# PlacaCalefactora_notUsed.net
KiCad netlist of a schematic drawn in EAGLE
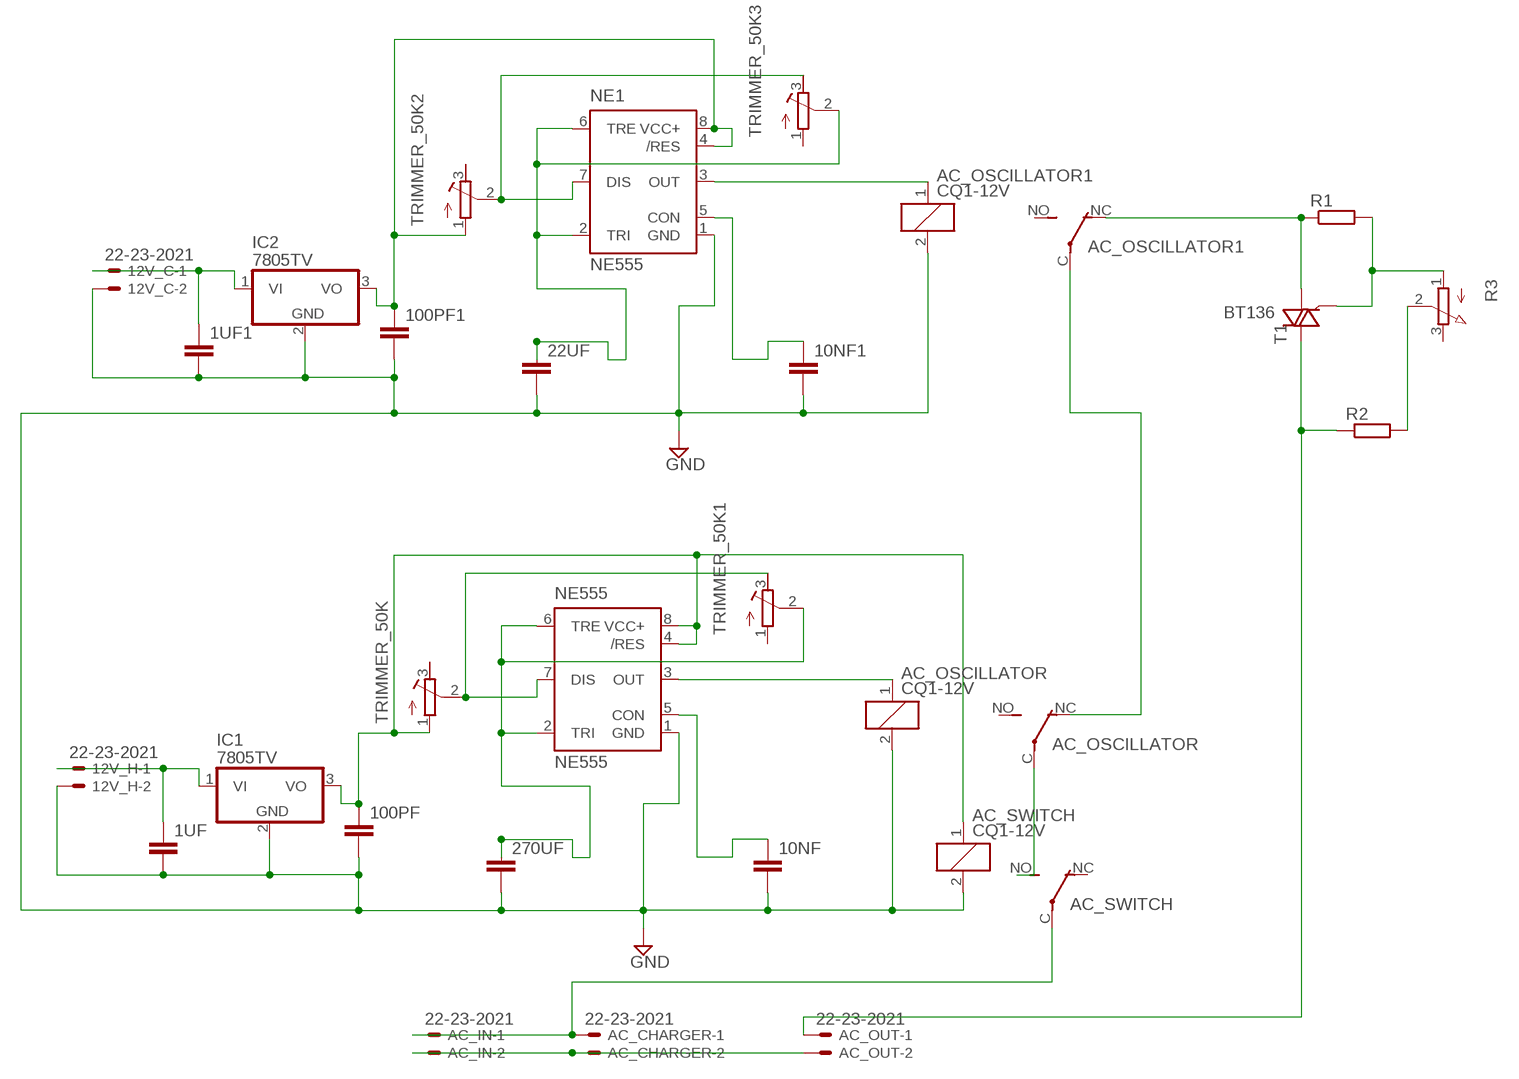
[diagram p0: schematic, sheet 1]

(export (version "E")
  (design (tool "Eeschema 10.0.6"))
  (components
    (comp (ref "1UF")
      (value "C7.5/3")
      (footprint "eagle-import:C7.5B3")
      (libsource (lib "eagle-import") (part "C7.5/3"))
    )
    (comp (ref "1UF1")
      (value "C7.5/3")
      (footprint "eagle-import:C7.5B3")
      (libsource (lib "eagle-import") (part "C7.5/3"))
    )
    (comp (ref "10NF")
      (value "C7.5/3")
      (footprint "eagle-import:C7.5B3")
      (libsource (lib "eagle-import") (part "C7.5/3"))
    )
    (comp (ref "10NF1")
      (value "C7.5/3")
      (footprint "eagle-import:C7.5B3")
      (libsource (lib "eagle-import") (part "C7.5/3"))
    )
    (comp (ref "12V_C")
      (value "22-23-2021")
      (footprint "eagle-import:22-23-2021")
      (fields (field (name "MF") "MOLEX"))
      (libsource (lib "eagle-import") (part "22-23-2021"))
    )
    (comp (ref "12V_H")
      (value "22-23-2021")
      (footprint "eagle-import:22-23-2021")
      (fields (field (name "MF") "MOLEX"))
      (libsource (lib "eagle-import") (part "22-23-2021"))
    )
    (comp (ref "22UF")
      (value "C7.5/3")
      (footprint "eagle-import:C7.5B3")
      (libsource (lib "eagle-import") (part "C7.5/3"))
    )
    (comp (ref "100PF")
      (value "C7.5/3")
      (footprint "eagle-import:C7.5B3")
      (libsource (lib "eagle-import") (part "C7.5/3"))
    )
    (comp (ref "100PF1")
      (value "C7.5/3")
      (footprint "eagle-import:C7.5B3")
      (libsource (lib "eagle-import") (part "C7.5/3"))
    )
    (comp (ref "270UF")
      (value "C7.5/3")
      (footprint "eagle-import:C7.5B3")
      (libsource (lib "eagle-import") (part "C7.5/3"))
    )
    (comp (ref "AC_CHARGER")
      (value "22-23-2021")
      (footprint "eagle-import:22-23-2021")
      (fields (field (name "MF") "MOLEX"))
      (libsource (lib "eagle-import") (part "22-23-2021"))
    )
    (comp (ref "AC_IN")
      (value "22-23-2021")
      (footprint "eagle-import:22-23-2021")
      (fields (field (name "MF") "MOLEX"))
      (libsource (lib "eagle-import") (part "22-23-2021"))
    )
    (comp (ref "AC_OSCILLATOR")
      (value "CQ1-12V")
      (footprint "eagle-import:CQ1")
      (libsource (lib "eagle-import") (part "CQ1-12V"))
    )
    (comp (ref "AC_OSCILLATOR1")
      (value "CQ1-12V")
      (footprint "eagle-import:CQ1")
      (libsource (lib "eagle-import") (part "CQ1-12V"))
    )
    (comp (ref "AC_OUT")
      (value "22-23-2021")
      (footprint "eagle-import:22-23-2021")
      (fields (field (name "MF") "MOLEX"))
      (libsource (lib "eagle-import") (part "22-23-2021"))
    )
    (comp (ref "AC_SWITCH")
      (value "CQ1-12V")
      (footprint "eagle-import:CQ1")
      (libsource (lib "eagle-import") (part "CQ1-12V"))
    )
    (comp (ref "IC1")
      (value "7805TV")
      (footprint "eagle-import:TO220V")
      (libsource (lib "eagle-import") (part "78TV05"))
    )
    (comp (ref "IC2")
      (value "7805TV")
      (footprint "eagle-import:TO220V")
      (libsource (lib "eagle-import") (part "78TV05"))
    )
    (comp (ref "NE1")
      (value "NE555")
      (footprint "eagle-import:DIL-08")
      (fields (field (name "MF") "Arrow Electronics") (field (name "MPN") "NE555N"))
      (libsource (lib "eagle-import") (part "NE555"))
    )
    (comp (ref "NE555")
      (value "NE555")
      (footprint "eagle-import:DIL-08")
      (fields (field (name "MF") "Arrow Electronics") (field (name "MPN") "NE555N"))
      (libsource (lib "eagle-import") (part "NE555"))
    )
    (comp (ref "R1")
      (value "R-EU_0204/7")
      (footprint "eagle-import:0204_7")
      (libsource (lib "eagle-import") (part "R-EU_0204/7"))
    )
    (comp (ref "R2")
      (value "R-EU_0204/7")
      (footprint "eagle-import:0204_7")
      (libsource (lib "eagle-import") (part "R-EU_0204/7"))
    )
    (comp (ref "R3")
      (value "3RP/1610N")
      (footprint "eagle-import:3RP_1610N")
      (libsource (lib "eagle-import") (part "3RP/1610N"))
    )
    (comp (ref "T1")
      (value "BT136")
      (footprint "eagle-import:TO220AB")
      (libsource (lib "eagle-import") (part "BT136"))
    )
    (comp (ref "TRIMMER_50K")
      (value "R-TRIMM64W")
      (footprint "eagle-import:RTRIM64W")
      (libsource (lib "eagle-import") (part "R-TRIMM64W"))
    )
    (comp (ref "TRIMMER_50K1")
      (value "R-TRIMM64W")
      (footprint "eagle-import:RTRIM64W")
      (libsource (lib "eagle-import") (part "R-TRIMM64W"))
    )
    (comp (ref "TRIMMER_50K2")
      (value "R-TRIMM64W")
      (footprint "eagle-import:RTRIM64W")
      (libsource (lib "eagle-import") (part "R-TRIMM64W"))
    )
    (comp (ref "TRIMMER_50K3")
      (value "R-TRIMM64W")
      (footprint "eagle-import:RTRIM64W")
      (libsource (lib "eagle-import") (part "R-TRIMM64W"))
    )
  )
  (nets
    (net (code "1") (name "GND") (class "Default")
      (node (ref "100PF") (pin "2") (pinfunction "2_2") (pintype "passive"))
      (node (ref "100PF1") (pin "2") (pinfunction "2_2") (pintype "passive"))
      (node (ref "10NF") (pin "2") (pinfunction "2_2") (pintype "passive"))
      (node (ref "10NF1") (pin "2") (pinfunction "2_2") (pintype "passive"))
      (node (ref "12V_C") (pin "2") (pinfunction "S_2") (pintype "passive"))
      (node (ref "12V_H") (pin "2") (pinfunction "S_2") (pintype "passive"))
      (node (ref "1UF") (pin "2") (pinfunction "2_2") (pintype "passive"))
      (node (ref "1UF1") (pin "2") (pinfunction "2_2") (pintype "passive"))
      (node (ref "22UF") (pin "2") (pinfunction "2_2") (pintype "passive"))
      (node (ref "270UF") (pin "2") (pinfunction "2_2") (pintype "passive"))
      (node (ref "AC_OSCILLATOR") (pin "2") (pinfunction "2_2") (pintype "passive"))
      (node (ref "AC_OSCILLATOR1") (pin "2") (pinfunction "2_2") (pintype "passive"))
      (node (ref "AC_SWITCH") (pin "2") (pinfunction "2_2") (pintype "passive"))
      (node (ref "IC1") (pin "2") (pinfunction "GND_2") (pintype "passive"))
      (node (ref "IC2") (pin "2") (pinfunction "GND_2") (pintype "passive"))
      (node (ref "NE1") (pin "1") (pinfunction "GND_1") (pintype "power_in"))
      (node (ref "NE555") (pin "1") (pinfunction "GND_1") (pintype "power_in"))
    )
    (net (code "2") (name "Net-(12V_CA-S)") (class "Default")
      (node (ref "12V_C") (pin "1") (pinfunction "S_1") (pintype "passive"))
      (node (ref "1UF1") (pin "1") (pinfunction "1_1") (pintype "passive"))
      (node (ref "IC2") (pin "1") (pinfunction "VI_1") (pintype "input"))
    )
    (net (code "3") (name "Net-(12V_HA-S)") (class "Default")
      (node (ref "12V_H") (pin "1") (pinfunction "S_1") (pintype "passive"))
      (node (ref "1UF") (pin "1") (pinfunction "1_1") (pintype "passive"))
      (node (ref "IC1") (pin "1") (pinfunction "VI_1") (pintype "input"))
    )
    (net (code "4") (name "Net-(AC_CHARGERA-S)") (class "Default")
      (node (ref "AC_CHARGER") (pin "1") (pinfunction "S_1") (pintype "passive"))
      (node (ref "AC_IN") (pin "1") (pinfunction "S_1") (pintype "passive"))
      (node (ref "AC_SWITCH") (pin "C") (pinfunction "P_C") (pintype "passive"))
    )
    (net (code "5") (name "Net-(AC_CHARGERB-S)") (class "Default")
      (node (ref "AC_CHARGER") (pin "2") (pinfunction "S_2") (pintype "passive"))
      (node (ref "AC_IN") (pin "2") (pinfunction "S_2") (pintype "passive"))
      (node (ref "AC_OUT") (pin "2") (pinfunction "S_2") (pintype "passive"))
    )
    (net (code "6") (name "Net-(AC_OSCILLATOR1B-O)") (class "Default")
      (node (ref "AC_OSCILLATOR1") (pin "NC") (pinfunction "O_NC") (pintype "passive"))
      (node (ref "R1") (pin "1") (pinfunction "1_1") (pintype "passive"))
      (node (ref "T1") (pin "1") (pinfunction "A1_1") (pintype "passive"))
    )
    (net (code "7") (name "Net-(AC_OSCILLATOR1B-P)") (class "Default")
      (node (ref "AC_OSCILLATOR") (pin "NC") (pinfunction "O_NC") (pintype "passive"))
      (node (ref "AC_OSCILLATOR1") (pin "C") (pinfunction "P_C") (pintype "passive"))
    )
    (net (code "8") (name "Net-(AC_OSCILLATORB-P)") (class "Default")
      (node (ref "AC_OSCILLATOR") (pin "C") (pinfunction "P_C") (pintype "passive"))
      (node (ref "AC_SWITCH") (pin "NO") (pinfunction "S_NO") (pintype "passive"))
    )
    (net (code "9") (name "Net-(AC_OUTA-S)") (class "Default")
      (node (ref "AC_OUT") (pin "1") (pinfunction "S_1") (pintype "passive"))
      (node (ref "R2") (pin "1") (pinfunction "1_1") (pintype "passive"))
      (node (ref "T1") (pin "2") (pinfunction "A2_2") (pintype "passive"))
    )
    (net (code "10") (name "Net-(IC1-VO)") (class "Default")
      (node (ref "100PF") (pin "1") (pinfunction "1_1") (pintype "passive"))
      (node (ref "AC_SWITCH") (pin "1") (pinfunction "1_1") (pintype "passive"))
      (node (ref "IC1") (pin "3") (pinfunction "VO_3") (pintype "passive"))
      (node (ref "NE555") (pin "4") (pinfunction "/RES_4") (pintype "input"))
      (node (ref "NE555") (pin "8") (pinfunction "VCC+_8") (pintype "power_in"))
      (node (ref "TRIMMER_50K") (pin "1") (pinfunction "A_1") (pintype "passive"))
    )
    (net (code "11") (name "Net-(IC2-VO)") (class "Default")
      (node (ref "100PF1") (pin "1") (pinfunction "1_1") (pintype "passive"))
      (node (ref "IC2") (pin "3") (pinfunction "VO_3") (pintype "passive"))
      (node (ref "NE1") (pin "4") (pinfunction "/RES_4") (pintype "input"))
      (node (ref "NE1") (pin "8") (pinfunction "VCC+_8") (pintype "power_in"))
      (node (ref "TRIMMER_50K2") (pin "1") (pinfunction "A_1") (pintype "passive"))
    )
    (net (code "12") (name "Net-(NE1-CON)") (class "Default")
      (node (ref "10NF1") (pin "1") (pinfunction "1_1") (pintype "passive"))
      (node (ref "NE1") (pin "5") (pinfunction "CON_5") (pintype "input"))
    )
    (net (code "13") (name "Net-(NE1-DIS)") (class "Default")
      (node (ref "NE1") (pin "7") (pinfunction "DIS_7") (pintype "input"))
      (node (ref "TRIMMER_50K2") (pin "2") (pinfunction "S_2") (pintype "passive"))
      (node (ref "TRIMMER_50K3") (pin "3") (pinfunction "E_3") (pintype "passive"))
    )
    (net (code "14") (name "Net-(NE1-OUT)") (class "Default")
      (node (ref "AC_OSCILLATOR1") (pin "1") (pinfunction "1_1") (pintype "passive"))
      (node (ref "NE1") (pin "3") (pinfunction "OUT_3") (pintype "output"))
    )
    (net (code "15") (name "Net-(NE1-TRE)") (class "Default")
      (node (ref "22UF") (pin "1") (pinfunction "1_1") (pintype "passive"))
      (node (ref "NE1") (pin "2") (pinfunction "TRI_2") (pintype "input"))
      (node (ref "NE1") (pin "6") (pinfunction "TRE_6") (pintype "input"))
      (node (ref "TRIMMER_50K3") (pin "2") (pinfunction "S_2") (pintype "passive"))
    )
    (net (code "16") (name "Net-(NE555-CON)") (class "Default")
      (node (ref "10NF") (pin "1") (pinfunction "1_1") (pintype "passive"))
      (node (ref "NE555") (pin "5") (pinfunction "CON_5") (pintype "input"))
    )
    (net (code "17") (name "Net-(NE555-DIS)") (class "Default")
      (node (ref "NE555") (pin "7") (pinfunction "DIS_7") (pintype "input"))
      (node (ref "TRIMMER_50K") (pin "2") (pinfunction "S_2") (pintype "passive"))
      (node (ref "TRIMMER_50K1") (pin "3") (pinfunction "E_3") (pintype "passive"))
    )
    (net (code "18") (name "Net-(NE555-OUT)") (class "Default")
      (node (ref "AC_OSCILLATOR") (pin "1") (pinfunction "1_1") (pintype "passive"))
      (node (ref "NE555") (pin "3") (pinfunction "OUT_3") (pintype "output"))
    )
    (net (code "19") (name "Net-(NE555-TRE)") (class "Default")
      (node (ref "270UF") (pin "1") (pinfunction "1_1") (pintype "passive"))
      (node (ref "NE555") (pin "2") (pinfunction "TRI_2") (pintype "input"))
      (node (ref "NE555") (pin "6") (pinfunction "TRE_6") (pintype "input"))
      (node (ref "TRIMMER_50K1") (pin "2") (pinfunction "S_2") (pintype "passive"))
    )
    (net (code "20") (name "Net-(R3-A)") (class "Default")
      (node (ref "R1") (pin "2") (pinfunction "2_2") (pintype "passive"))
      (node (ref "R3") (pin "1") (pinfunction "A_1") (pintype "passive"))
      (node (ref "T1") (pin "3") (pinfunction "G_3") (pintype "passive"))
    )
    (net (code "21") (name "Net-(R3-S)") (class "Default")
      (node (ref "R2") (pin "2") (pinfunction "2_2") (pintype "passive"))
      (node (ref "R3") (pin "2") (pinfunction "S_2") (pintype "passive"))
    )
    (net (code "22") (name "unconnected-(AC_OSCILLATOR1B-S-PadNO)") (class "Default")
      (node (ref "AC_OSCILLATOR1") (pin "NO") (pinfunction "S_NO") (pintype "passive"))
    )
    (net (code "23") (name "unconnected-(AC_OSCILLATORB-S-PadNO)") (class "Default")
      (node (ref "AC_OSCILLATOR") (pin "NO") (pinfunction "S_NO") (pintype "passive"))
    )
    (net (code "24") (name "unconnected-(AC_SWITCHB-O-PadNC)") (class "Default")
      (node (ref "AC_SWITCH") (pin "NC") (pinfunction "O_NC") (pintype "passive"))
    )
    (net (code "25") (name "unconnected-(R3-E-Pad3)") (class "Default")
      (node (ref "R3") (pin "3") (pinfunction "E_3") (pintype "passive"))
    )
    (net (code "26") (name "unconnected-(TRIMMER_50K-E-Pad3)") (class "Default")
      (node (ref "TRIMMER_50K") (pin "3") (pinfunction "E_3") (pintype "passive"))
    )
    (net (code "27") (name "unconnected-(TRIMMER_50K1-A-Pad1)") (class "Default")
      (node (ref "TRIMMER_50K1") (pin "1") (pinfunction "A_1") (pintype "passive"))
    )
    (net (code "28") (name "unconnected-(TRIMMER_50K2-E-Pad3)") (class "Default")
      (node (ref "TRIMMER_50K2") (pin "3") (pinfunction "E_3") (pintype "passive"))
    )
    (net (code "29") (name "unconnected-(TRIMMER_50K3-A-Pad1)") (class "Default")
      (node (ref "TRIMMER_50K3") (pin "1") (pinfunction "A_1") (pintype "passive"))
    )
  )
)
